# PowerReg.net
KiCad netlist of a schematic drawn in Altium Designer
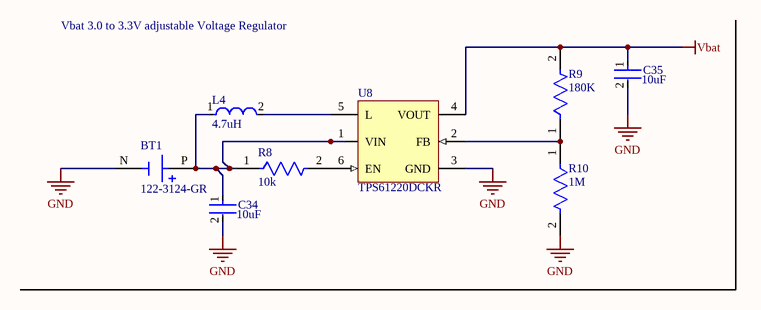
[diagram p0: PowerReg.SchDoc]

(export (version "E")
  (design (tool "Eeschema 10.0.6"))
  (components
    (comp (ref "BT1")
      (value "122-3124-GR")
      (footprint "BAT_122-3124-GR")
      (description "Coin Cell Battery Holders CR2477 COIN CELL HL")
      (fields (field (name "MF") "Eagle Plastic Devices"))
      (libsource (lib "George Evanisko") (part "122-3124-GR"))
    )
    (comp (ref "C34")
      (value "10uF")
      (footprint "FP-CGA6P-IPC_B")
      (description "Cap Ceramic 10uF 16V X7R 20% Pad SMD 1210 +125°C Automotive T/R")
      (fields (field (name "TOLERANCE") "20%"))
      (libsource (lib "Altium Content Vault") (part "b4654b650e69147ec39a6b967a45e02"))
    )
    (comp (ref "C35")
      (value "10uF")
      (footprint "FP-CGA6P-IPC_B")
      (description "Cap Ceramic 10uF 16V X7R 20% Pad SMD 1210 +125°C Automotive T/R")
      (fields (field (name "TOLERANCE") "20%"))
      (libsource (lib "Altium Content Vault") (part "b4654b650e69147ec39a6b967a45e02"))
    )
    (comp (ref "L4")
      (value "4.7uH")
      (footprint "FP-LBMF1608-0_8-0_2-MFG")
      (description "SMD Inductors 4.7uH ±20% 0.11A 0.312Ω 0603")
      (fields (field (name "TOLERANCE") "20%"))
      (libsource (lib "Altium Content Vault") (part "725321dda6339637d4d059423bc1c3c"))
    )
    (comp (ref "R8")
      (value "10k")
      (footprint "FP-CPF0603-MFG")
      (description "RES SMD 10KΩ 0.5% 1/16W 0603")
      (fields
        (field (name "OCTOPART") "https://octopart.com/cpf0603d10ke-te+connectivity-22737789")
        (field (name "MANUFACTURER") "TE Connectivity")
      )
      (libsource (lib "Altium Content Vault") (part "1029c3af85768c4190bb7ad29bc67b5"))
    )
    (comp (ref "R9")
      (value "180K")
      (footprint "FP-CRGP0603-IPC_C")
      (description "CRGP0603 180KΩ 0.25W ±100ppm/°C 1% 50V")
      (fields (field (name "MANUFACTURER PART NUMBER") "CRGP0603F180K") (field (name "MANUFACTURER") "TE"))
      (libsource (lib "Altium Content Vault") (part "1029c3af85768c4190bb7ad29bc67b5"))
    )
    (comp (ref "R10")
      (value "1M")
      (footprint "FP-CRGP0603-IPC_C")
      (description "RES 1M OHM 1% 1/4W 0603")
      (fields (field (name "TOLERANCE") "1%"))
      (libsource (lib "Altium Content Vault") (part "1029c3af85768c4190bb7ad29bc67b5"))
    )
    (comp (ref "U8")
      (value "TPS61220DCKR")
      (footprint "DCK0006A_L")
      (fields (field (name "MANUFACTURER") "Texas Instruments"))
      (libsource (lib "Altium Content Vault") (part "TI-TPS61220DCK6"))
    )
  )
  (nets
    (net (code "1") (name "GND") (class "Default")
      (node (ref "BT1") (pin "N") (pinfunction "NEG_N") (pintype "passive"))
      (node (ref "C34") (pin "2") (pinfunction "2_2") (pintype "passive"))
      (node (ref "C35") (pin "2") (pinfunction "2_2") (pintype "passive"))
      (node (ref "R10") (pin "2") (pinfunction "2_2") (pintype "passive"))
      (node (ref "U8") (pin "3") (pinfunction "GND_3") (pintype "power_in"))
    )
    (net (code "2") (name "Net-(BT1-POS)") (class "Default")
      (node (ref "BT1") (pin "P") (pinfunction "POS_P") (pintype "passive"))
      (node (ref "C34") (pin "1") (pinfunction "1_1") (pintype "passive"))
      (node (ref "L4") (pin "1") (pinfunction "1_1") (pintype "passive"))
      (node (ref "R8") (pin "1") (pinfunction "1_1") (pintype "passive"))
      (node (ref "U8") (pin "1") (pinfunction "VIN_1") (pintype "power_in"))
    )
    (net (code "3") (name "Net-(U8-EN)") (class "Default")
      (node (ref "R8") (pin "2") (pinfunction "2_2") (pintype "passive"))
      (node (ref "U8") (pin "6") (pinfunction "EN_6") (pintype "input"))
    )
    (net (code "4") (name "Net-(U8-FB)") (class "Default")
      (node (ref "R10") (pin "1") (pinfunction "1_1") (pintype "passive"))
      (node (ref "R9") (pin "1") (pinfunction "1_1") (pintype "passive"))
      (node (ref "U8") (pin "2") (pinfunction "FB_2") (pintype "input"))
    )
    (net (code "5") (name "Net-(U8-L)") (class "Default")
      (node (ref "L4") (pin "2") (pinfunction "2_2") (pintype "passive"))
      (node (ref "U8") (pin "5") (pinfunction "L_5") (pintype "power_in"))
    )
    (net (code "6") (name "Vbat") (class "Default")
      (node (ref "C35") (pin "1") (pinfunction "1_1") (pintype "passive"))
      (node (ref "R9") (pin "2") (pinfunction "2_2") (pintype "passive"))
      (node (ref "U8") (pin "4") (pinfunction "VOUT_4") (pintype "power_in"))
    )
  )
)
